# pot-boardE.net
KiCad netlist of a schematic drawn in EAGLE
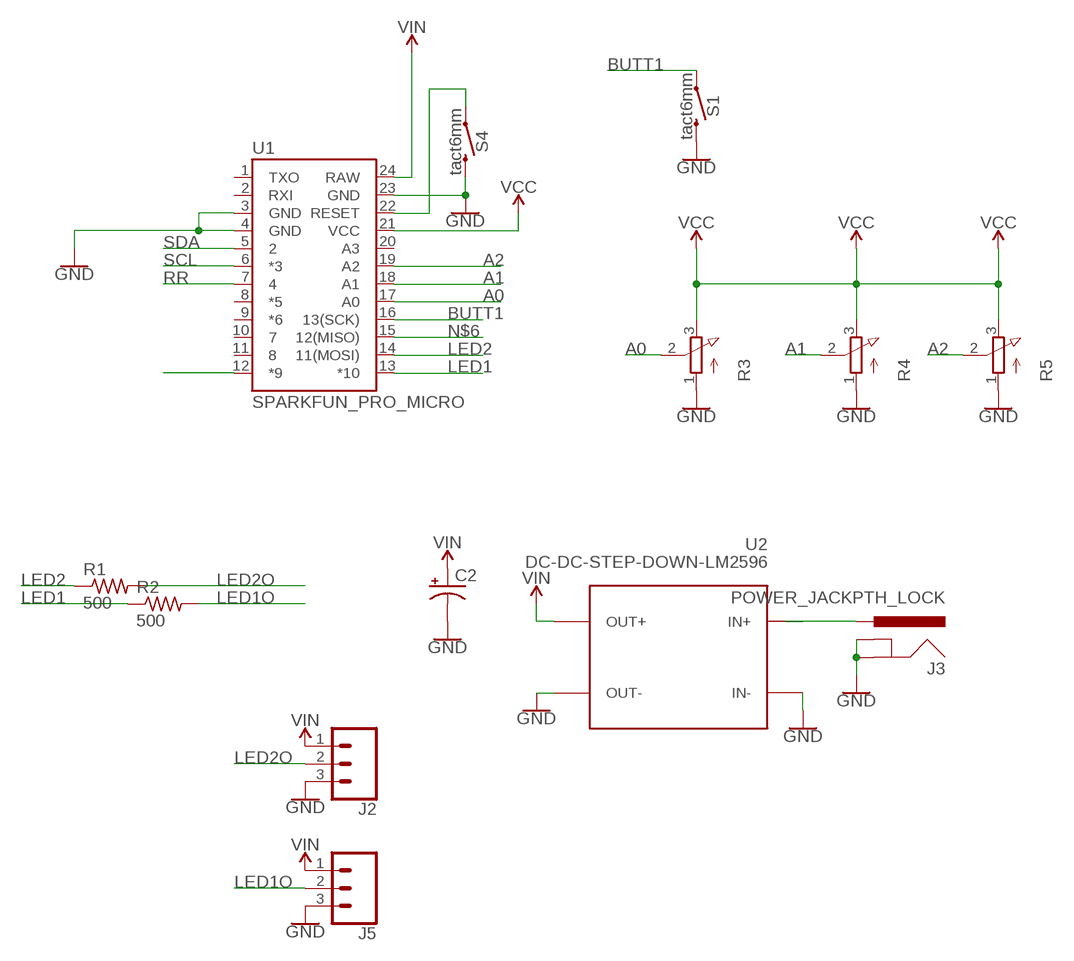
[diagram p0: schematic, sheet 1]

(export (version "E")
  (design (tool "Eeschema 10.0.6"))
  (components
    (comp (ref "C2")
      (value "CPOL-USE3.5-8")
      (footprint "eagle-import:E3,5-8")
      (libsource (lib "eagle-import") (part "CPOL-USE3.5-8"))
    )
    (comp (ref "J2")
      (value "CONN_03")
      (footprint "eagle-import:1X03")
      (libsource (lib "eagle-import") (part "CONN_03"))
    )
    (comp (ref "J3")
      (value "POWER_JACKPTH_LOCK")
      (footprint "eagle-import:POWER_JACK_PTH_LOCK")
      (libsource (lib "eagle-import") (part "POWER_JACKPTH_LOCK"))
    )
    (comp (ref "J5")
      (value "CONN_03")
      (footprint "eagle-import:1X03")
      (libsource (lib "eagle-import") (part "CONN_03"))
    )
    (comp (ref "R1")
      (value "500")
      (footprint "eagle-import:R0805")
      (libsource (lib "eagle-import") (part "R-US_R0805"))
    )
    (comp (ref "R2")
      (value "500")
      (footprint "eagle-import:R0805")
      (libsource (lib "eagle-import") (part "R-US_R0805"))
    )
    (comp (ref "R3")
      (value "3RP/1610N")
      (footprint "eagle-import:3RP_1610N")
      (libsource (lib "eagle-import") (part "3RP/1610N"))
    )
    (comp (ref "R4")
      (value "3RP/1610N")
      (footprint "eagle-import:3RP_1610N")
      (libsource (lib "eagle-import") (part "3RP/1610N"))
    )
    (comp (ref "R5")
      (value "3RP/1610N")
      (footprint "eagle-import:3RP_1610N")
      (libsource (lib "eagle-import") (part "3RP/1610N"))
    )
    (comp (ref "S1")
      (value "tact6mm")
      (footprint "eagle-import:TACTILE_SWITCH_PTH_6.0MM")
      (libsource (lib "eagle-import") (part "MOMENTARY-SWITCH-SPST-PTH-6.0MM"))
    )
    (comp (ref "S4")
      (value "tact6mm")
      (footprint "eagle-import:TACTILE_SWITCH_PTH_6.0MM")
      (libsource (lib "eagle-import") (part "MOMENTARY-SWITCH-SPST-PTH-6.0MM"))
    )
    (comp (ref "U1")
      (value "SPARKFUN_PRO_MICRO")
      (footprint "eagle-import:SPARKFUN_PRO_MICRO")
      (libsource (lib "eagle-import") (part "SPARKFUN_PRO_MICRO"))
    )
    (comp (ref "U2")
      (value "DC-DC-STEP-DOWN-LM2596")
      (footprint "eagle-import:DC-DC-STEP-DOWN-LM2596")
      (libsource (lib "eagle-import") (part "DC-DC-STEP-DOWN-LM2596"))
    )
  )
  (nets
    (net (code "1") (name "/A0") (class "Default")
      (node (ref "R3") (pin "2") (pinfunction "S_2") (pintype "passive"))
      (node (ref "U1") (pin "17") (pinfunction "A0_17") (pintype "bidirectional"))
    )
    (net (code "2") (name "/A1") (class "Default")
      (node (ref "R4") (pin "2") (pinfunction "S_2") (pintype "passive"))
      (node (ref "U1") (pin "18") (pinfunction "A1_18") (pintype "bidirectional"))
    )
    (net (code "3") (name "/A2") (class "Default")
      (node (ref "R5") (pin "2") (pinfunction "S_2") (pintype "passive"))
      (node (ref "U1") (pin "19") (pinfunction "A2_19") (pintype "bidirectional"))
    )
    (net (code "4") (name "/BUTT1") (class "Default")
      (node (ref "S1") (pin "1") (pinfunction "1_1") (pintype "passive"))
      (node (ref "U1") (pin "16") (pinfunction "13(SCK)_16") (pintype "bidirectional"))
    )
    (net (code "5") (name "/LED1") (class "Default")
      (node (ref "R2") (pin "1") (pinfunction "1_1") (pintype "passive"))
      (node (ref "U1") (pin "13") (pinfunction "*10_13") (pintype "bidirectional"))
    )
    (net (code "6") (name "/LED1O") (class "Default")
      (node (ref "J5") (pin "2") (pinfunction "2_2") (pintype "passive"))
      (node (ref "R2") (pin "2") (pinfunction "2_2") (pintype "passive"))
    )
    (net (code "7") (name "/LED2") (class "Default")
      (node (ref "R1") (pin "1") (pinfunction "1_1") (pintype "passive"))
      (node (ref "U1") (pin "14") (pinfunction "11(MOSI)_14") (pintype "bidirectional"))
    )
    (net (code "8") (name "/LED2O") (class "Default")
      (node (ref "J2") (pin "2") (pinfunction "2_2") (pintype "passive"))
      (node (ref "R1") (pin "2") (pinfunction "2_2") (pintype "passive"))
    )
    (net (code "9") (name "/N$6") (class "Default")
      (node (ref "U1") (pin "15") (pinfunction "12(MISO)_15") (pintype "bidirectional"))
    )
    (net (code "10") (name "/RR") (class "Default")
      (node (ref "U1") (pin "7") (pinfunction "4_7") (pintype "bidirectional"))
    )
    (net (code "11") (name "/SCL") (class "Default")
      (node (ref "U1") (pin "6") (pinfunction "*3_6") (pintype "bidirectional"))
    )
    (net (code "12") (name "/SDA") (class "Default")
      (node (ref "U1") (pin "5") (pinfunction "2_5") (pintype "bidirectional"))
    )
    (net (code "13") (name "GND") (class "Default")
      (node (ref "C2") (pin "-") (pinfunction "-_-") (pintype "passive"))
      (node (ref "J2") (pin "3") (pinfunction "3_3") (pintype "passive"))
      (node (ref "J3") (pin "GND") (pinfunction "GND_GND") (pintype "bidirectional"))
      (node (ref "J3") (pin "GNDBREAK") (pinfunction "GNDBREAK_GNDBREAK") (pintype "bidirectional"))
      (node (ref "J5") (pin "3") (pinfunction "3_3") (pintype "passive"))
      (node (ref "R3") (pin "1") (pinfunction "A_1") (pintype "passive"))
      (node (ref "R4") (pin "1") (pinfunction "A_1") (pintype "passive"))
      (node (ref "R5") (pin "1") (pinfunction "A_1") (pintype "passive"))
      (node (ref "S1") (pin "3") (pinfunction "2_3") (pintype "passive"))
      (node (ref "S4") (pin "3") (pinfunction "2_3") (pintype "passive"))
      (node (ref "U1") (pin "23") (pinfunction "GND_23") (pintype "power_in"))
      (node (ref "U1") (pin "3") (pinfunction "GND_3") (pintype "power_in"))
      (node (ref "U1") (pin "4") (pinfunction "GND_4") (pintype "power_in"))
      (node (ref "U2") (pin "IN-") (pinfunction "IN-_IN-") (pintype "bidirectional"))
      (node (ref "U2") (pin "OUT-") (pinfunction "OUT-_OUT-") (pintype "bidirectional"))
    )
    (net (code "14") (name "Net-(J3-PadPWR)") (class "Default")
      (node (ref "J3") (pin "PWR") (pinfunction "PWR_PWR") (pintype "bidirectional"))
      (node (ref "U2") (pin "IN+") (pinfunction "IN+_IN+") (pintype "bidirectional"))
    )
    (net (code "15") (name "Net-(U1-RESET)") (class "Default")
      (node (ref "S4") (pin "1") (pinfunction "1_1") (pintype "passive"))
      (node (ref "U1") (pin "22") (pinfunction "RESET_22") (pintype "bidirectional"))
    )
    (net (code "16") (name "VCC") (class "Default")
      (node (ref "R3") (pin "3") (pinfunction "E_3") (pintype "passive"))
      (node (ref "R4") (pin "3") (pinfunction "E_3") (pintype "passive"))
      (node (ref "R5") (pin "3") (pinfunction "E_3") (pintype "passive"))
      (node (ref "U1") (pin "21") (pinfunction "VCC_21") (pintype "power_in"))
    )
    (net (code "17") (name "VIN") (class "Default")
      (node (ref "C2") (pin "+") (pinfunction "+_+") (pintype "passive"))
      (node (ref "J2") (pin "1") (pinfunction "1_1") (pintype "passive"))
      (node (ref "J5") (pin "1") (pinfunction "1_1") (pintype "passive"))
      (node (ref "U1") (pin "24") (pinfunction "RAW_24") (pintype "power_in"))
      (node (ref "U2") (pin "OUT+") (pinfunction "OUT+_OUT+") (pintype "bidirectional"))
    )
    (net (code "18") (name "unconnected-(U1-*5-Pad8)") (class "Default")
      (node (ref "U1") (pin "8") (pinfunction "*5_8") (pintype "bidirectional"))
    )
    (net (code "19") (name "unconnected-(U1-*6-Pad9)") (class "Default")
      (node (ref "U1") (pin "9") (pinfunction "*6_9") (pintype "bidirectional"))
    )
    (net (code "20") (name "unconnected-(U1-*9-Pad12)") (class "Default")
      (node (ref "U1") (pin "12") (pinfunction "*9_12") (pintype "bidirectional"))
    )
    (net (code "21") (name "unconnected-(U1-7-Pad10)") (class "Default")
      (node (ref "U1") (pin "10") (pinfunction "7_10") (pintype "bidirectional"))
    )
    (net (code "22") (name "unconnected-(U1-8-Pad11)") (class "Default")
      (node (ref "U1") (pin "11") (pinfunction "8_11") (pintype "bidirectional"))
    )
    (net (code "23") (name "unconnected-(U1-A3-Pad20)") (class "Default")
      (node (ref "U1") (pin "20") (pinfunction "A3_20") (pintype "bidirectional"))
    )
    (net (code "24") (name "unconnected-(U1-RXI-Pad2)") (class "Default")
      (node (ref "U1") (pin "2") (pinfunction "RXI_2") (pintype "bidirectional"))
    )
    (net (code "25") (name "unconnected-(U1-TXO-Pad1)") (class "Default")
      (node (ref "U1") (pin "1") (pinfunction "TXO_1") (pintype "bidirectional"))
    )
  )
)
